# custom_line_V1_mux3.net
KiCad netlist of a schematic drawn in Altium Designer
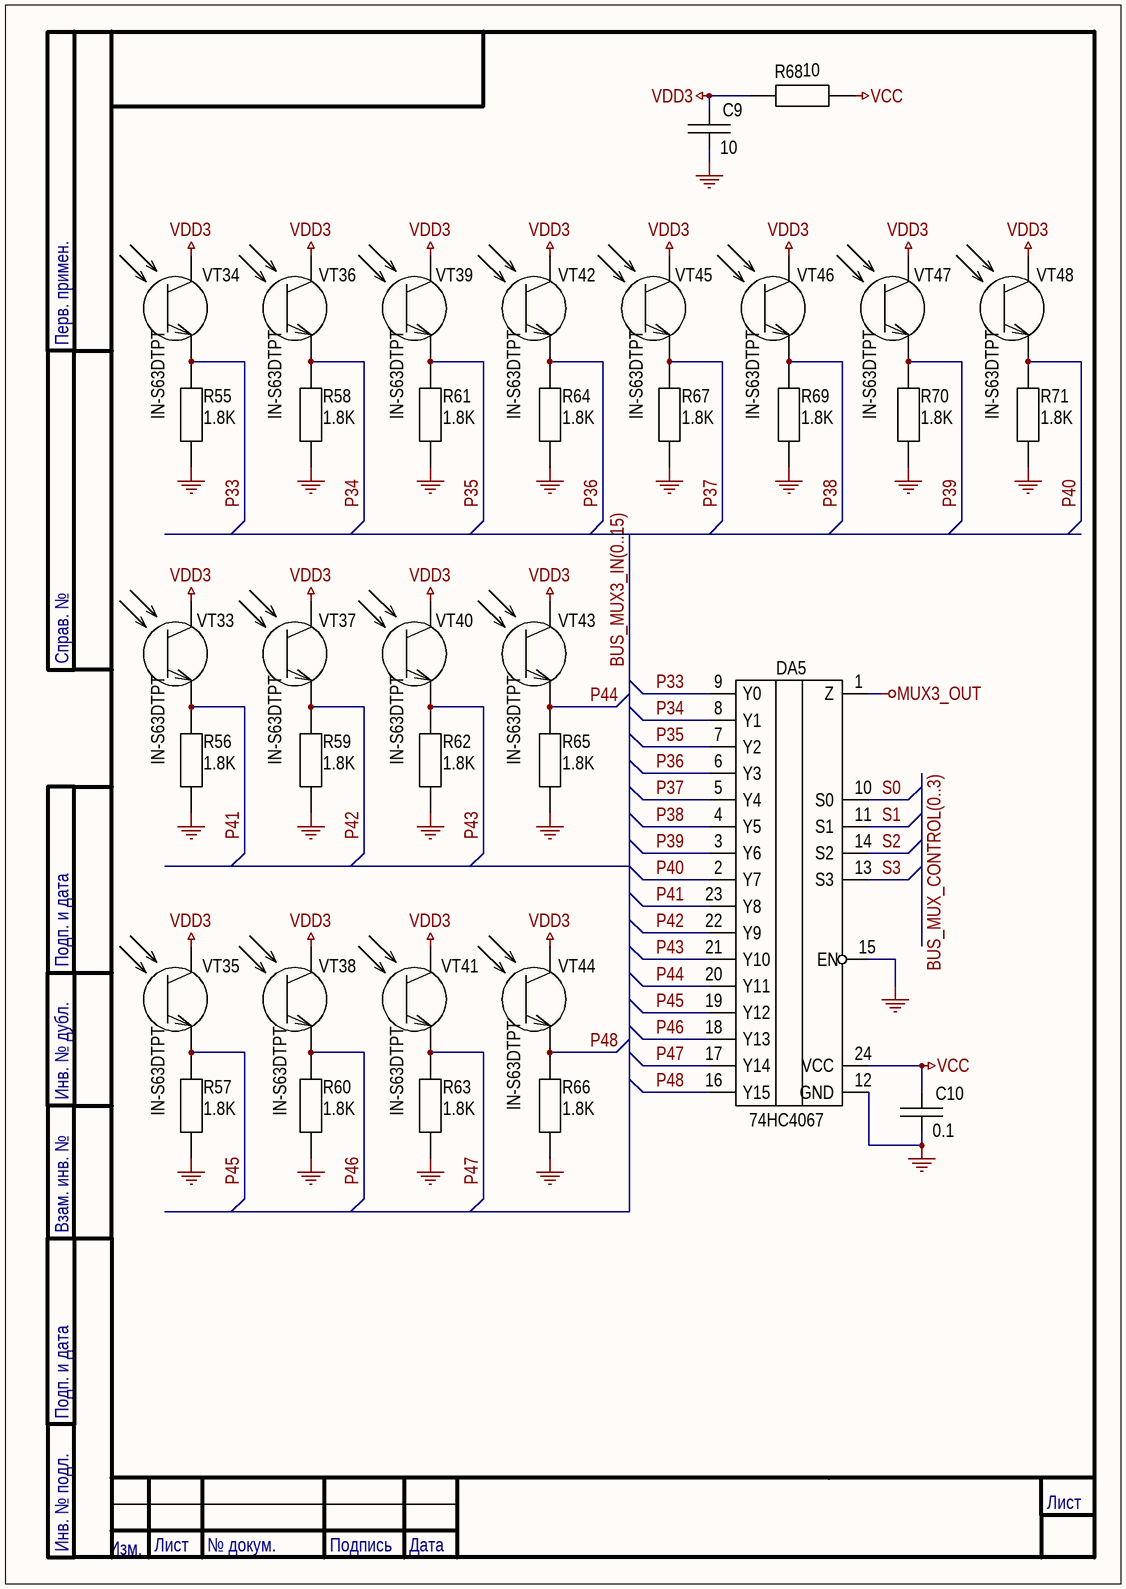
[diagram p0: custom_line_V1_mux3.SchDoc]

(export (version "E")
  (design (tool "Eeschema 10.0.6"))
  (components
    (comp (ref "C9") (value "10") (footprint "CC_0805") (libsource (lib "my_discrete_new") (part "C")))
    (comp (ref "C10") (value "0.1") (footprint "CC_0603") (libsource (lib "my_discrete_new") (part "C")))
    (comp (ref "DA5")
      (value "74HC4067")
      (footprint "TSSOP-24")
      (description "74HC4067PW")
      (fields (field (name "TYPE") "74HC4067"))
      (libsource (lib "my_microschems_new") (part "74HCT4067"))
    )
    (comp (ref "R55")
      (value "1.8K")
      (footprint "RC_0603_SMALL")
      (fields (field (name "POWER") "0.125W"))
      (libsource (lib "my_discrete_new") (part "R"))
    )
    (comp (ref "R56")
      (value "1.8K")
      (footprint "RC_0603_SMALL")
      (fields (field (name "POWER") "0.125W"))
      (libsource (lib "my_discrete_new") (part "R"))
    )
    (comp (ref "R57")
      (value "1.8K")
      (footprint "RC_0603_SMALL")
      (fields (field (name "POWER") "0.125W"))
      (libsource (lib "my_discrete_new") (part "R"))
    )
    (comp (ref "R58")
      (value "1.8K")
      (footprint "RC_0603_SMALL")
      (fields (field (name "POWER") "0.125W"))
      (libsource (lib "my_discrete_new") (part "R"))
    )
    (comp (ref "R59")
      (value "1.8K")
      (footprint "RC_0603_SMALL")
      (fields (field (name "POWER") "0.125W"))
      (libsource (lib "my_discrete_new") (part "R"))
    )
    (comp (ref "R60")
      (value "1.8K")
      (footprint "RC_0603_SMALL")
      (fields (field (name "POWER") "0.125W"))
      (libsource (lib "my_discrete_new") (part "R"))
    )
    (comp (ref "R61")
      (value "1.8K")
      (footprint "RC_0603_SMALL")
      (fields (field (name "POWER") "0.125W"))
      (libsource (lib "my_discrete_new") (part "R"))
    )
    (comp (ref "R62")
      (value "1.8K")
      (footprint "RC_0603_SMALL")
      (fields (field (name "POWER") "0.125W"))
      (libsource (lib "my_discrete_new") (part "R"))
    )
    (comp (ref "R63")
      (value "1.8K")
      (footprint "RC_0603_SMALL")
      (fields (field (name "POWER") "0.125W"))
      (libsource (lib "my_discrete_new") (part "R"))
    )
    (comp (ref "R64")
      (value "1.8K")
      (footprint "RC_0603_SMALL")
      (fields (field (name "POWER") "0.125W"))
      (libsource (lib "my_discrete_new") (part "R"))
    )
    (comp (ref "R65")
      (value "1.8K")
      (footprint "RC_0603_SMALL")
      (fields (field (name "POWER") "0.125W"))
      (libsource (lib "my_discrete_new") (part "R"))
    )
    (comp (ref "R66")
      (value "1.8K")
      (footprint "RC_0603_SMALL")
      (fields (field (name "POWER") "0.125W"))
      (libsource (lib "my_discrete_new") (part "R"))
    )
    (comp (ref "R67")
      (value "1.8K")
      (footprint "RC_0603_SMALL")
      (fields (field (name "POWER") "0.125W"))
      (libsource (lib "my_discrete_new") (part "R"))
    )
    (comp (ref "R68")
      (value "10")
      (footprint "RC_0603_SMALL")
      (fields (field (name "POWER") "0.125W"))
      (libsource (lib "my_discrete_new") (part "R"))
    )
    (comp (ref "R69")
      (value "1.8K")
      (footprint "RC_0603_SMALL")
      (fields (field (name "POWER") "0.125W"))
      (libsource (lib "my_discrete_new") (part "R"))
    )
    (comp (ref "R70")
      (value "1.8K")
      (footprint "RC_0603_SMALL")
      (fields (field (name "POWER") "0.125W"))
      (libsource (lib "my_discrete_new") (part "R"))
    )
    (comp (ref "R71")
      (value "1.8K")
      (footprint "RC_0603_SMALL")
      (fields (field (name "POWER") "0.125W"))
      (libsource (lib "my_discrete_new") (part "R"))
    )
    (comp (ref "VT33")
      (value "IN-S63DTPT")
      (footprint "LED_0603")
      (description "Phototransistor (Inolux)")
      (libsource (lib "my_discrete_new") (part "phototransistor"))
    )
    (comp (ref "VT34")
      (value "IN-S63DTPT")
      (footprint "LED_0603")
      (description "Phototransistor (Inolux)")
      (libsource (lib "my_discrete_new") (part "phototransistor"))
    )
    (comp (ref "VT35")
      (value "IN-S63DTPT")
      (footprint "LED_0603")
      (description "Phototransistor (Inolux)")
      (libsource (lib "my_discrete_new") (part "phototransistor"))
    )
    (comp (ref "VT36")
      (value "IN-S63DTPT")
      (footprint "LED_0603")
      (description "Phototransistor (Inolux)")
      (libsource (lib "my_discrete_new") (part "phototransistor"))
    )
    (comp (ref "VT37")
      (value "IN-S63DTPT")
      (footprint "LED_0603")
      (description "Phototransistor (Inolux)")
      (libsource (lib "my_discrete_new") (part "phototransistor"))
    )
    (comp (ref "VT38")
      (value "IN-S63DTPT")
      (footprint "LED_0603")
      (description "Phototransistor (Inolux)")
      (libsource (lib "my_discrete_new") (part "phototransistor"))
    )
    (comp (ref "VT39")
      (value "IN-S63DTPT")
      (footprint "LED_0603")
      (description "Phototransistor (Inolux)")
      (libsource (lib "my_discrete_new") (part "phototransistor"))
    )
    (comp (ref "VT40")
      (value "IN-S63DTPT")
      (footprint "LED_0603")
      (description "Phototransistor (Inolux)")
      (libsource (lib "my_discrete_new") (part "phototransistor"))
    )
    (comp (ref "VT41")
      (value "IN-S63DTPT")
      (footprint "LED_0603")
      (description "Phototransistor (Inolux)")
      (libsource (lib "my_discrete_new") (part "phototransistor"))
    )
    (comp (ref "VT42")
      (value "IN-S63DTPT")
      (footprint "LED_0603")
      (description "Phototransistor (Inolux)")
      (libsource (lib "my_discrete_new") (part "phototransistor"))
    )
    (comp (ref "VT43")
      (value "IN-S63DTPT")
      (footprint "LED_0603")
      (description "Phototransistor (Inolux)")
      (libsource (lib "my_discrete_new") (part "phototransistor"))
    )
    (comp (ref "VT44")
      (value "IN-S63DTPT")
      (footprint "LED_0603")
      (description "Phototransistor (Inolux)")
      (libsource (lib "my_discrete_new") (part "phototransistor"))
    )
    (comp (ref "VT45")
      (value "IN-S63DTPT")
      (footprint "LED_0603")
      (description "Phototransistor (Inolux)")
      (libsource (lib "my_discrete_new") (part "phototransistor"))
    )
    (comp (ref "VT46")
      (value "IN-S63DTPT")
      (footprint "LED_0603")
      (description "Phototransistor (Inolux)")
      (libsource (lib "my_discrete_new") (part "phototransistor"))
    )
    (comp (ref "VT47")
      (value "IN-S63DTPT")
      (footprint "LED_0603")
      (description "Phototransistor (Inolux)")
      (libsource (lib "my_discrete_new") (part "phototransistor"))
    )
    (comp (ref "VT48")
      (value "IN-S63DTPT")
      (footprint "LED_0603")
      (description "Phototransistor (Inolux)")
      (libsource (lib "my_discrete_new") (part "phototransistor"))
    )
  )
  (nets
    (net (code "3") (name "/P33") (class "Default")
      (node (ref "DA5") (pin "9") (pinfunction "Y0_9") (pintype "passive"))
      (node (ref "R55") (pin "2") (pinfunction "2_2") (pintype "passive"))
      (node (ref "VT34") (pin "2") (pinfunction "E_2") (pintype "passive"))
    )
    (net (code "4") (name "/P34") (class "Default")
      (node (ref "DA5") (pin "8") (pinfunction "Y1_8") (pintype "passive"))
      (node (ref "R58") (pin "2") (pinfunction "2_2") (pintype "passive"))
      (node (ref "VT36") (pin "2") (pinfunction "E_2") (pintype "passive"))
    )
    (net (code "5") (name "/P35") (class "Default")
      (node (ref "DA5") (pin "7") (pinfunction "Y2_7") (pintype "passive"))
      (node (ref "R61") (pin "2") (pinfunction "2_2") (pintype "passive"))
      (node (ref "VT39") (pin "2") (pinfunction "E_2") (pintype "passive"))
    )
    (net (code "6") (name "/P36") (class "Default")
      (node (ref "DA5") (pin "6") (pinfunction "Y3_6") (pintype "passive"))
      (node (ref "R64") (pin "2") (pinfunction "2_2") (pintype "passive"))
      (node (ref "VT42") (pin "2") (pinfunction "E_2") (pintype "passive"))
    )
    (net (code "7") (name "/P37") (class "Default")
      (node (ref "DA5") (pin "5") (pinfunction "Y4_5") (pintype "passive"))
      (node (ref "R67") (pin "2") (pinfunction "2_2") (pintype "passive"))
      (node (ref "VT45") (pin "2") (pinfunction "E_2") (pintype "passive"))
    )
    (net (code "8") (name "/P38") (class "Default")
      (node (ref "DA5") (pin "4") (pinfunction "Y5_4") (pintype "passive"))
      (node (ref "R69") (pin "2") (pinfunction "2_2") (pintype "passive"))
      (node (ref "VT46") (pin "2") (pinfunction "E_2") (pintype "passive"))
    )
    (net (code "9") (name "/P39") (class "Default")
      (node (ref "DA5") (pin "3") (pinfunction "Y6_3") (pintype "passive"))
      (node (ref "R70") (pin "2") (pinfunction "2_2") (pintype "passive"))
      (node (ref "VT47") (pin "2") (pinfunction "E_2") (pintype "passive"))
    )
    (net (code "10") (name "/P40") (class "Default")
      (node (ref "DA5") (pin "2") (pinfunction "Y7_2") (pintype "passive"))
      (node (ref "R71") (pin "2") (pinfunction "2_2") (pintype "passive"))
      (node (ref "VT48") (pin "2") (pinfunction "E_2") (pintype "passive"))
    )
    (net (code "11") (name "/P41") (class "Default")
      (node (ref "DA5") (pin "23") (pinfunction "Y8_23") (pintype "passive"))
      (node (ref "R56") (pin "2") (pinfunction "2_2") (pintype "passive"))
      (node (ref "VT33") (pin "2") (pinfunction "E_2") (pintype "passive"))
    )
    (net (code "12") (name "/P42") (class "Default")
      (node (ref "DA5") (pin "22") (pinfunction "Y9_22") (pintype "passive"))
      (node (ref "R59") (pin "2") (pinfunction "2_2") (pintype "passive"))
      (node (ref "VT37") (pin "2") (pinfunction "E_2") (pintype "passive"))
    )
    (net (code "13") (name "/P43") (class "Default")
      (node (ref "DA5") (pin "21") (pinfunction "Y10_21") (pintype "passive"))
      (node (ref "R62") (pin "2") (pinfunction "2_2") (pintype "passive"))
      (node (ref "VT40") (pin "2") (pinfunction "E_2") (pintype "passive"))
    )
    (net (code "14") (name "/P44") (class "Default")
      (node (ref "DA5") (pin "20") (pinfunction "Y11_20") (pintype "passive"))
      (node (ref "R65") (pin "2") (pinfunction "2_2") (pintype "passive"))
      (node (ref "VT43") (pin "2") (pinfunction "E_2") (pintype "passive"))
    )
    (net (code "15") (name "/P45") (class "Default")
      (node (ref "DA5") (pin "19") (pinfunction "Y12_19") (pintype "passive"))
      (node (ref "R57") (pin "2") (pinfunction "2_2") (pintype "passive"))
      (node (ref "VT35") (pin "2") (pinfunction "E_2") (pintype "passive"))
    )
    (net (code "16") (name "/P46") (class "Default")
      (node (ref "DA5") (pin "18") (pinfunction "Y13_18") (pintype "passive"))
      (node (ref "R60") (pin "2") (pinfunction "2_2") (pintype "passive"))
      (node (ref "VT38") (pin "2") (pinfunction "E_2") (pintype "passive"))
    )
    (net (code "17") (name "/P47") (class "Default")
      (node (ref "DA5") (pin "17") (pinfunction "Y14_17") (pintype "passive"))
      (node (ref "R63") (pin "2") (pinfunction "2_2") (pintype "passive"))
      (node (ref "VT41") (pin "2") (pinfunction "E_2") (pintype "passive"))
    )
    (net (code "18") (name "/P48") (class "Default")
      (node (ref "DA5") (pin "16") (pinfunction "Y15_16") (pintype "passive"))
      (node (ref "R66") (pin "2") (pinfunction "2_2") (pintype "passive"))
      (node (ref "VT44") (pin "2") (pinfunction "E_2") (pintype "passive"))
    )
    (net (code "19") (name "/S0") (class "Default")
      (node (ref "DA5") (pin "10") (pinfunction "S0_10") (pintype "passive"))
    )
    (net (code "20") (name "/S1") (class "Default")
      (node (ref "DA5") (pin "11") (pinfunction "S1_11") (pintype "passive"))
    )
    (net (code "21") (name "/S2") (class "Default")
      (node (ref "DA5") (pin "14") (pinfunction "S2_14") (pintype "passive"))
    )
    (net (code "22") (name "/S3") (class "Default")
      (node (ref "DA5") (pin "13") (pinfunction "S3_13") (pintype "passive"))
    )
    (net (code "25") (name "GND") (class "Default")
      (node (ref "C10") (pin "1") (pinfunction "1_1") (pintype "passive"))
      (node (ref "C9") (pin "1") (pinfunction "1_1") (pintype "passive"))
      (node (ref "DA5") (pin "12") (pinfunction "GND_12") (pintype "power_in"))
      (node (ref "DA5") (pin "15") (pinfunction "EN_15") (pintype "passive"))
      (node (ref "R55") (pin "1") (pinfunction "1_1") (pintype "passive"))
      (node (ref "R56") (pin "1") (pinfunction "1_1") (pintype "passive"))
      (node (ref "R57") (pin "1") (pinfunction "1_1") (pintype "passive"))
      (node (ref "R58") (pin "1") (pinfunction "1_1") (pintype "passive"))
      (node (ref "R59") (pin "1") (pinfunction "1_1") (pintype "passive"))
      (node (ref "R60") (pin "1") (pinfunction "1_1") (pintype "passive"))
      (node (ref "R61") (pin "1") (pinfunction "1_1") (pintype "passive"))
      (node (ref "R62") (pin "1") (pinfunction "1_1") (pintype "passive"))
      (node (ref "R63") (pin "1") (pinfunction "1_1") (pintype "passive"))
      (node (ref "R64") (pin "1") (pinfunction "1_1") (pintype "passive"))
      (node (ref "R65") (pin "1") (pinfunction "1_1") (pintype "passive"))
      (node (ref "R66") (pin "1") (pinfunction "1_1") (pintype "passive"))
      (node (ref "R67") (pin "1") (pinfunction "1_1") (pintype "passive"))
      (node (ref "R69") (pin "1") (pinfunction "1_1") (pintype "passive"))
      (node (ref "R70") (pin "1") (pinfunction "1_1") (pintype "passive"))
      (node (ref "R71") (pin "1") (pinfunction "1_1") (pintype "passive"))
    )
    (net (code "26") (name "MUX3_OUT") (class "Default")
      (node (ref "DA5") (pin "1") (pinfunction "Z_1") (pintype "passive"))
    )
    (net (code "27") (name "VCC") (class "Default")
      (node (ref "C10") (pin "2") (pinfunction "2_2") (pintype "passive"))
      (node (ref "DA5") (pin "24") (pinfunction "VCC_24") (pintype "power_in"))
      (node (ref "R68") (pin "1") (pinfunction "1_1") (pintype "passive"))
    )
    (net (code "28") (name "VDD3") (class "Default")
      (node (ref "C9") (pin "2") (pinfunction "2_2") (pintype "passive"))
      (node (ref "R68") (pin "2") (pinfunction "2_2") (pintype "passive"))
      (node (ref "VT33") (pin "1") (pinfunction "C_1") (pintype "passive"))
      (node (ref "VT34") (pin "1") (pinfunction "C_1") (pintype "passive"))
      (node (ref "VT35") (pin "1") (pinfunction "C_1") (pintype "passive"))
      (node (ref "VT36") (pin "1") (pinfunction "C_1") (pintype "passive"))
      (node (ref "VT37") (pin "1") (pinfunction "C_1") (pintype "passive"))
      (node (ref "VT38") (pin "1") (pinfunction "C_1") (pintype "passive"))
      (node (ref "VT39") (pin "1") (pinfunction "C_1") (pintype "passive"))
      (node (ref "VT40") (pin "1") (pinfunction "C_1") (pintype "passive"))
      (node (ref "VT41") (pin "1") (pinfunction "C_1") (pintype "passive"))
      (node (ref "VT42") (pin "1") (pinfunction "C_1") (pintype "passive"))
      (node (ref "VT43") (pin "1") (pinfunction "C_1") (pintype "passive"))
      (node (ref "VT44") (pin "1") (pinfunction "C_1") (pintype "passive"))
      (node (ref "VT45") (pin "1") (pinfunction "C_1") (pintype "passive"))
      (node (ref "VT46") (pin "1") (pinfunction "C_1") (pintype "passive"))
      (node (ref "VT47") (pin "1") (pinfunction "C_1") (pintype "passive"))
      (node (ref "VT48") (pin "1") (pinfunction "C_1") (pintype "passive"))
    )
  )
)
